# LilyPad_Protoboard_Small.net
KiCad netlist of a schematic drawn in EAGLE
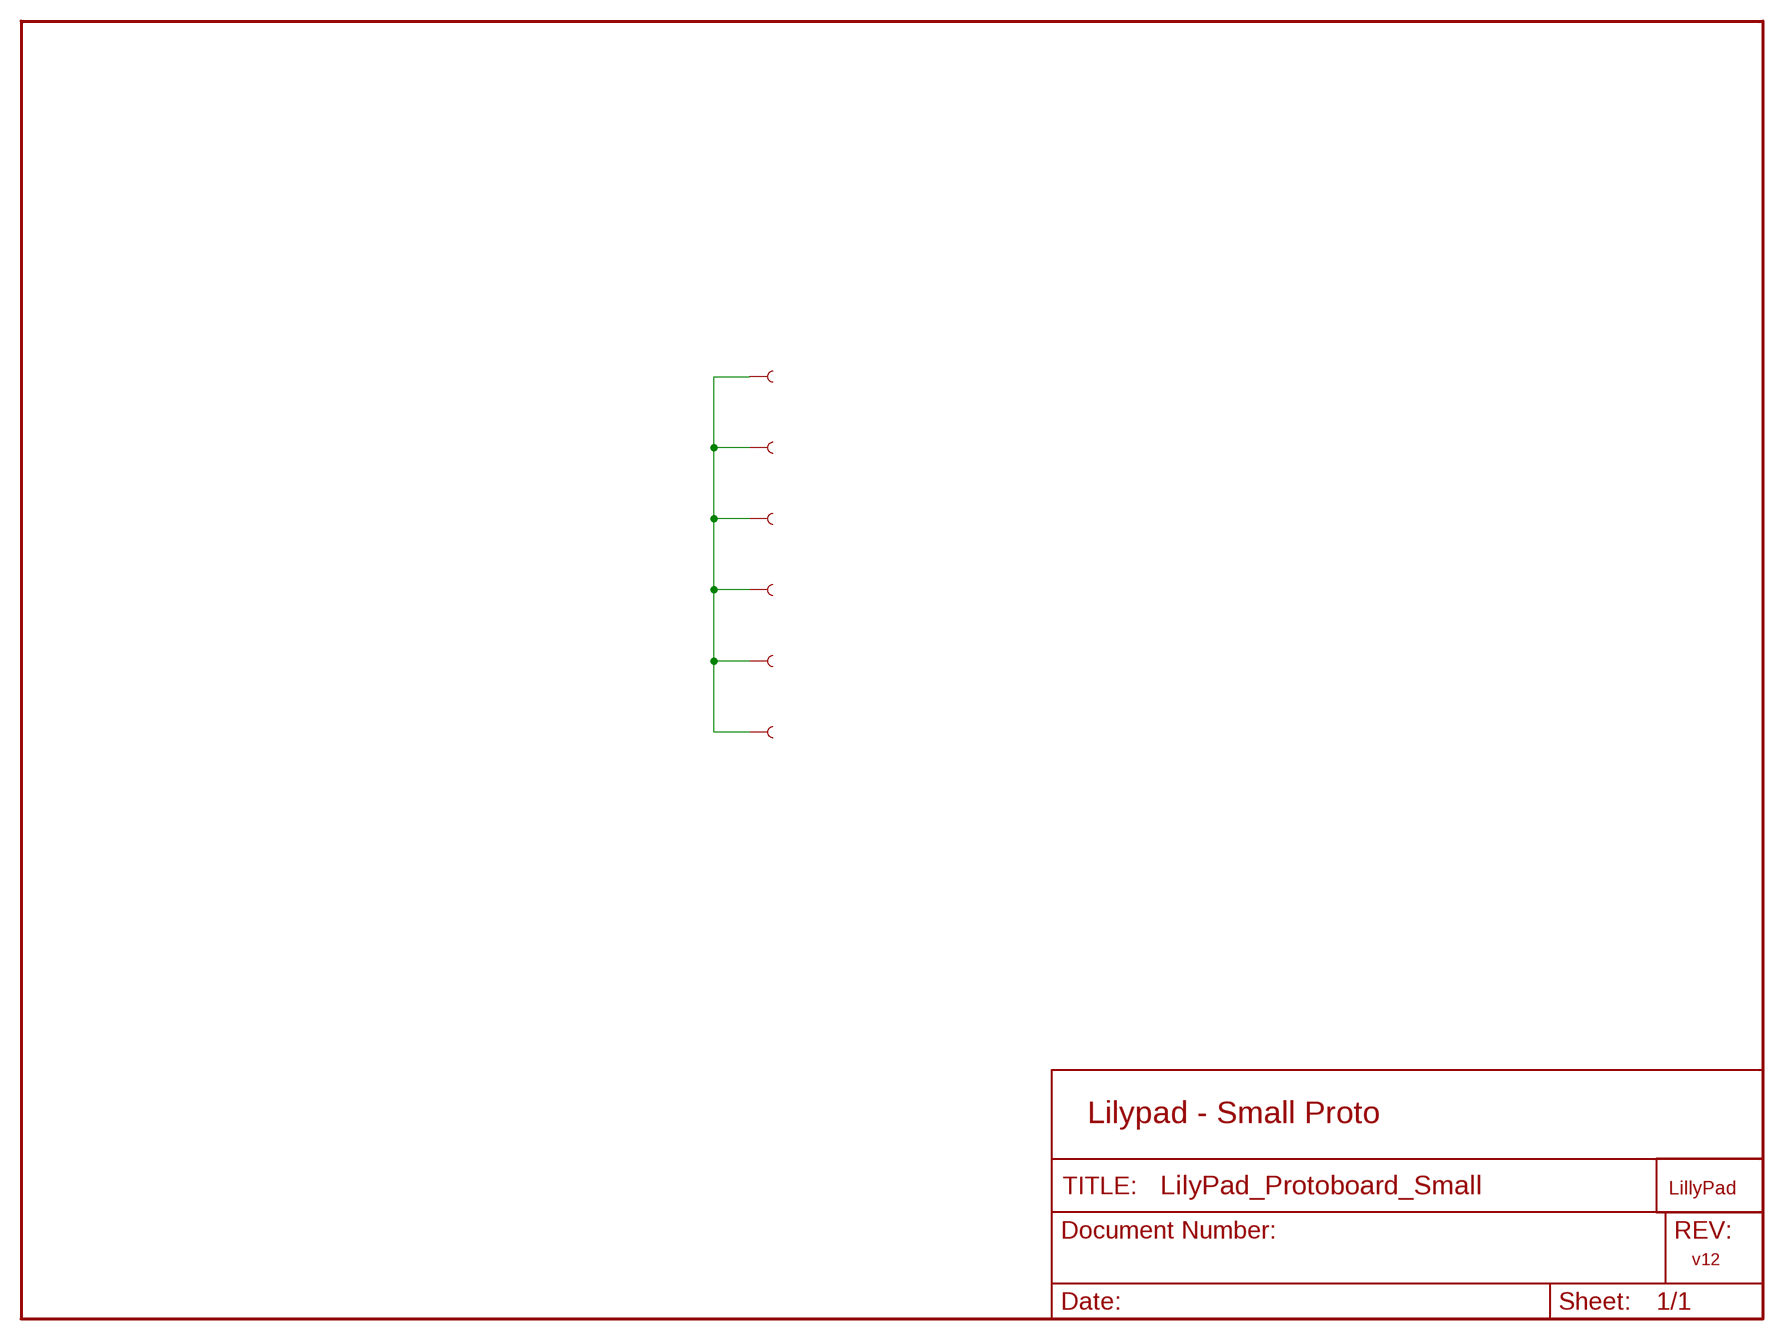
[diagram p0: schematic, sheet 1]

(export (version "E")
  (design (tool "Eeschema 10.0.6"))
  (components
    (comp (ref "U$2")
      (value "LOGO-LPL")
      (footprint "eagle-import:LOGO-L")
      (libsource (lib "eagle-import") (part "LOGO-LPL"))
    )
    (comp (ref "U$3")
      (value "SEWTAP6")
      (footprint "eagle-import:PETAL-SMALL-2SIDE")
      (libsource (lib "eagle-import") (part "SEWTAP6"))
    )
    (comp (ref "U$4")
      (value "SEWTAP6")
      (footprint "eagle-import:PETAL-SMALL-2SIDE")
      (libsource (lib "eagle-import") (part "SEWTAP6"))
    )
    (comp (ref "U$5")
      (value "SEWTAP6")
      (footprint "eagle-import:PETAL-SMALL-2SIDE")
      (libsource (lib "eagle-import") (part "SEWTAP6"))
    )
    (comp (ref "U$8")
      (value "SEWTAP6")
      (footprint "eagle-import:PETAL-SMALL-2SIDE")
      (libsource (lib "eagle-import") (part "SEWTAP6"))
    )
    (comp (ref "U$9")
      (value "SEWTAP6")
      (footprint "eagle-import:PETAL-SMALL-2SIDE")
      (libsource (lib "eagle-import") (part "SEWTAP6"))
    )
    (comp (ref "U$10")
      (value "SEWTAP6")
      (footprint "eagle-import:PETAL-SMALL-2SIDE")
      (libsource (lib "eagle-import") (part "SEWTAP6"))
    )
  )
  (nets
    (net (code "1") (name "Net-(U$10-Pad1)") (class "Default")
      (node (ref "U$10") (pin "1") (pinfunction "1_1") (pintype "bidirectional"))
      (node (ref "U$3") (pin "1") (pinfunction "1_1") (pintype "bidirectional"))
      (node (ref "U$4") (pin "1") (pinfunction "1_1") (pintype "bidirectional"))
      (node (ref "U$5") (pin "1") (pinfunction "1_1") (pintype "bidirectional"))
      (node (ref "U$8") (pin "1") (pinfunction "1_1") (pintype "bidirectional"))
      (node (ref "U$9") (pin "1") (pinfunction "1_1") (pintype "bidirectional"))
    )
  )
)
